# EDMCB.net
KiCad netlist of a schematic drawn in EAGLE
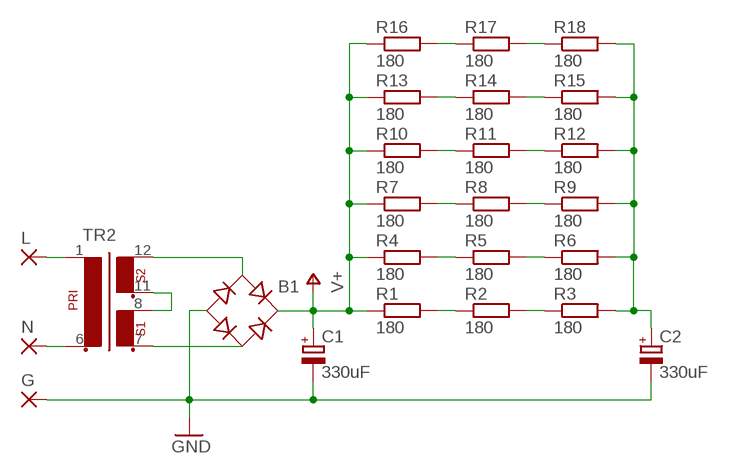
[diagram p0: schematic, sheet 1]

(export (version "E")
  (design (tool "Eeschema 10.0.6"))
  (components
    (comp (ref "B1")
      (value "RECTIFIER-FB32")
      (footprint "eagle-import:FB32")
      (libsource (lib "eagle-import") (part "RECTIFIER-FB32"))
    )
    (comp (ref "C1")
      (value "330uF")
      (footprint "eagle-import:SANYO-OSCON_H")
      (libsource (lib "eagle-import") (part "CPOL-EUSANYO_H"))
    )
    (comp (ref "C2")
      (value "330uF")
      (footprint "eagle-import:SANYO-OSCON_H")
      (libsource (lib "eagle-import") (part "CPOL-EUSANYO_H"))
    )
    (comp (ref "G")
      (value "WIREPAD4,16O1,6")
      (footprint "eagle-import:4,16O1,6")
      (libsource (lib "eagle-import") (part "WIREPAD4,16O1,6"))
    )
    (comp (ref "L")
      (value "WIREPAD4,16O1,6")
      (footprint "eagle-import:4,16O1,6")
      (libsource (lib "eagle-import") (part "WIREPAD4,16O1,6"))
    )
    (comp (ref "N")
      (value "WIREPAD4,16O1,6")
      (footprint "eagle-import:4,16O1,6")
      (libsource (lib "eagle-import") (part "WIREPAD4,16O1,6"))
    )
    (comp (ref "R1")
      (value "180")
      (footprint "eagle-import:VTA52")
      (libsource (lib "eagle-import") (part "R-EU_VTA52"))
    )
    (comp (ref "R2")
      (value "180")
      (footprint "eagle-import:VTA52")
      (libsource (lib "eagle-import") (part "R-EU_VTA52"))
    )
    (comp (ref "R3")
      (value "180")
      (footprint "eagle-import:VTA52")
      (libsource (lib "eagle-import") (part "R-EU_VTA52"))
    )
    (comp (ref "R4")
      (value "180")
      (footprint "eagle-import:VTA52")
      (libsource (lib "eagle-import") (part "R-EU_VTA52"))
    )
    (comp (ref "R5")
      (value "180")
      (footprint "eagle-import:VTA52")
      (libsource (lib "eagle-import") (part "R-EU_VTA52"))
    )
    (comp (ref "R6")
      (value "180")
      (footprint "eagle-import:VTA52")
      (libsource (lib "eagle-import") (part "R-EU_VTA52"))
    )
    (comp (ref "R7")
      (value "180")
      (footprint "eagle-import:VTA52")
      (libsource (lib "eagle-import") (part "R-EU_VTA52"))
    )
    (comp (ref "R8")
      (value "180")
      (footprint "eagle-import:VTA52")
      (libsource (lib "eagle-import") (part "R-EU_VTA52"))
    )
    (comp (ref "R9")
      (value "180")
      (footprint "eagle-import:VTA52")
      (libsource (lib "eagle-import") (part "R-EU_VTA52"))
    )
    (comp (ref "R10")
      (value "180")
      (footprint "eagle-import:VTA52")
      (libsource (lib "eagle-import") (part "R-EU_VTA52"))
    )
    (comp (ref "R11")
      (value "180")
      (footprint "eagle-import:VTA52")
      (libsource (lib "eagle-import") (part "R-EU_VTA52"))
    )
    (comp (ref "R12")
      (value "180")
      (footprint "eagle-import:VTA52")
      (libsource (lib "eagle-import") (part "R-EU_VTA52"))
    )
    (comp (ref "R13")
      (value "180")
      (footprint "eagle-import:VTA52")
      (libsource (lib "eagle-import") (part "R-EU_VTA52"))
    )
    (comp (ref "R14")
      (value "180")
      (footprint "eagle-import:VTA52")
      (libsource (lib "eagle-import") (part "R-EU_VTA52"))
    )
    (comp (ref "R15")
      (value "180")
      (footprint "eagle-import:VTA52")
      (libsource (lib "eagle-import") (part "R-EU_VTA52"))
    )
    (comp (ref "R16")
      (value "180")
      (footprint "eagle-import:VTA52")
      (libsource (lib "eagle-import") (part "R-EU_VTA52"))
    )
    (comp (ref "R17")
      (value "180")
      (footprint "eagle-import:VTA52")
      (libsource (lib "eagle-import") (part "R-EU_VTA52"))
    )
    (comp (ref "R18")
      (value "180")
      (footprint "eagle-import:VTA52")
      (libsource (lib "eagle-import") (part "R-EU_VTA52"))
    )
    (comp (ref "TR2")
      (value "EI48-2")
      (footprint "eagle-import:EI48-2")
      (libsource (lib "eagle-import") (part "EI48-2"))
    )
  )
  (nets
    (net (code "1") (name "GND") (class "Default")
      (node (ref "B1") (pin "-") (pinfunction "-_-") (pintype "passive"))
      (node (ref "C1") (pin "-") (pinfunction "-_-") (pintype "passive"))
      (node (ref "C2") (pin "-") (pinfunction "-_-") (pintype "passive"))
      (node (ref "G") (pin "1") (pinfunction "P_1") (pintype "passive"))
    )
    (net (code "2") (name "Net-(C2-Pad+)") (class "Default")
      (node (ref "C2") (pin "+") (pinfunction "+_+") (pintype "passive"))
      (node (ref "R12") (pin "2") (pinfunction "2_2") (pintype "passive"))
      (node (ref "R15") (pin "2") (pinfunction "2_2") (pintype "passive"))
      (node (ref "R18") (pin "2") (pinfunction "2_2") (pintype "passive"))
      (node (ref "R3") (pin "2") (pinfunction "2_2") (pintype "passive"))
      (node (ref "R6") (pin "2") (pinfunction "2_2") (pintype "passive"))
      (node (ref "R9") (pin "2") (pinfunction "2_2") (pintype "passive"))
    )
    (net (code "3") (name "Net-(L-P)") (class "Default")
      (node (ref "L") (pin "1") (pinfunction "P_1") (pintype "passive"))
      (node (ref "TR2") (pin "1") (pinfunction "1_1") (pintype "passive"))
    )
    (net (code "4") (name "Net-(N-P)") (class "Default")
      (node (ref "N") (pin "1") (pinfunction "P_1") (pintype "passive"))
      (node (ref "TR2") (pin "6") (pinfunction "2_6") (pintype "passive"))
    )
    (net (code "5") (name "Net-(R1-Pad2)") (class "Default")
      (node (ref "R1") (pin "2") (pinfunction "2_2") (pintype "passive"))
      (node (ref "R2") (pin "1") (pinfunction "1_1") (pintype "passive"))
    )
    (net (code "6") (name "Net-(R2-Pad2)") (class "Default")
      (node (ref "R2") (pin "2") (pinfunction "2_2") (pintype "passive"))
      (node (ref "R3") (pin "1") (pinfunction "1_1") (pintype "passive"))
    )
    (net (code "7") (name "Net-(R4-Pad2)") (class "Default")
      (node (ref "R4") (pin "2") (pinfunction "2_2") (pintype "passive"))
      (node (ref "R5") (pin "1") (pinfunction "1_1") (pintype "passive"))
    )
    (net (code "8") (name "Net-(R5-Pad2)") (class "Default")
      (node (ref "R5") (pin "2") (pinfunction "2_2") (pintype "passive"))
      (node (ref "R6") (pin "1") (pinfunction "1_1") (pintype "passive"))
    )
    (net (code "9") (name "Net-(R7-Pad2)") (class "Default")
      (node (ref "R7") (pin "2") (pinfunction "2_2") (pintype "passive"))
      (node (ref "R8") (pin "1") (pinfunction "1_1") (pintype "passive"))
    )
    (net (code "10") (name "Net-(R8-Pad2)") (class "Default")
      (node (ref "R8") (pin "2") (pinfunction "2_2") (pintype "passive"))
      (node (ref "R9") (pin "1") (pinfunction "1_1") (pintype "passive"))
    )
    (net (code "11") (name "Net-(R10-Pad2)") (class "Default")
      (node (ref "R10") (pin "2") (pinfunction "2_2") (pintype "passive"))
      (node (ref "R11") (pin "1") (pinfunction "1_1") (pintype "passive"))
    )
    (net (code "12") (name "Net-(R11-Pad2)") (class "Default")
      (node (ref "R11") (pin "2") (pinfunction "2_2") (pintype "passive"))
      (node (ref "R12") (pin "1") (pinfunction "1_1") (pintype "passive"))
    )
    (net (code "13") (name "Net-(R13-Pad2)") (class "Default")
      (node (ref "R13") (pin "2") (pinfunction "2_2") (pintype "passive"))
      (node (ref "R14") (pin "1") (pinfunction "1_1") (pintype "passive"))
    )
    (net (code "14") (name "Net-(R14-Pad2)") (class "Default")
      (node (ref "R14") (pin "2") (pinfunction "2_2") (pintype "passive"))
      (node (ref "R15") (pin "1") (pinfunction "1_1") (pintype "passive"))
    )
    (net (code "15") (name "Net-(R16-Pad2)") (class "Default")
      (node (ref "R16") (pin "2") (pinfunction "2_2") (pintype "passive"))
      (node (ref "R17") (pin "1") (pinfunction "1_1") (pintype "passive"))
    )
    (net (code "16") (name "Net-(R17-Pad2)") (class "Default")
      (node (ref "R17") (pin "2") (pinfunction "2_2") (pintype "passive"))
      (node (ref "R18") (pin "1") (pinfunction "1_1") (pintype "passive"))
    )
    (net (code "17") (name "Net-(TR2-3)") (class "Default")
      (node (ref "B1") (pin "AC2") (pinfunction "AC2_AC2") (pintype "passive"))
      (node (ref "TR2") (pin "7") (pinfunction "3_7") (pintype "passive"))
    )
    (net (code "18") (name "Net-(TR2-4)") (class "Default")
      (node (ref "TR2") (pin "11") (pinfunction "5_11") (pintype "passive"))
      (node (ref "TR2") (pin "8") (pinfunction "4_8") (pintype "passive"))
    )
    (net (code "19") (name "Net-(TR2-6)") (class "Default")
      (node (ref "B1") (pin "AC1") (pinfunction "AC1_AC1") (pintype "passive"))
      (node (ref "TR2") (pin "12") (pinfunction "6_12") (pintype "passive"))
    )
    (net (code "20") (name "V+") (class "Default")
      (node (ref "B1") (pin "+") (pinfunction "+_+") (pintype "passive"))
      (node (ref "C1") (pin "+") (pinfunction "+_+") (pintype "passive"))
      (node (ref "R1") (pin "1") (pinfunction "1_1") (pintype "passive"))
      (node (ref "R10") (pin "1") (pinfunction "1_1") (pintype "passive"))
      (node (ref "R13") (pin "1") (pinfunction "1_1") (pintype "passive"))
      (node (ref "R16") (pin "1") (pinfunction "1_1") (pintype "passive"))
      (node (ref "R4") (pin "1") (pinfunction "1_1") (pintype "passive"))
      (node (ref "R7") (pin "1") (pinfunction "1_1") (pintype "passive"))
    )
  )
)
